# XB900.net
KiCad netlist of a schematic drawn in Altium Designer
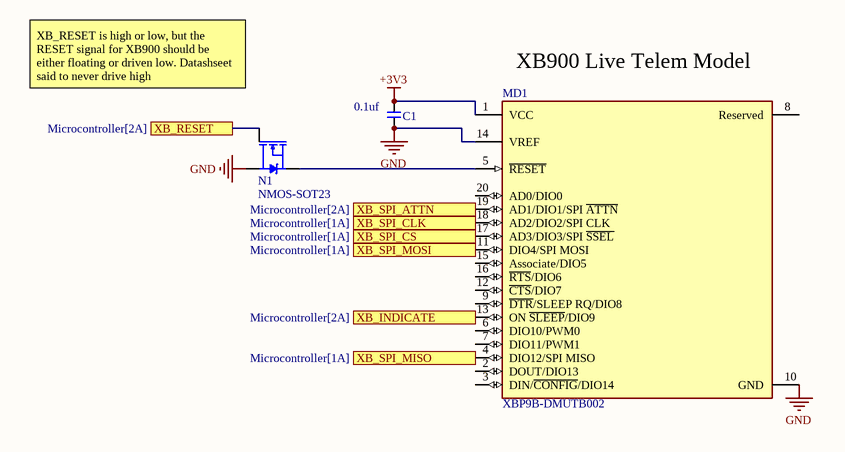
[diagram p0: XB900.SchDoc]

(export (version "E")
  (design (tool "Eeschema 10.0.6"))
  (components
    (comp (ref "C1")
      (value "0.1uf")
      (footprint "CAP-0603")
      (fields (field (name "SOURCE") "ife19_Elec_Library.SchLib"))
      (libsource (lib "Illini Formula Electric") (part "CAP-0603"))
    )
    (comp (ref "MD1")
      (value "XBP9B-DMUTB002")
      (footprint "FP-XBP9B-DMUTB002-MFG")
      (description "RX TXRX MOD ISM < 1GHZ U.FL TH")
      (libsource (lib "Altium Content Vault") (part "053d8e65a610ce00d52093c0e212ca3"))
    )
    (comp (ref "N1")
      (value "NMOS-SOT23")
      (footprint "SOT23")
      (fields (field (name "SOURCE") "ife19_Elec_Library.SchLib"))
      (libsource (lib "Illini Formula Electric") (part "NMOS-SOT23"))
    )
  )
  (nets
    (net (code "1") (name "+3V3") (class "Default")
      (node (ref "C1") (pin "2") (pinfunction "2_2") (pintype "passive"))
      (node (ref "MD1") (pin "1") (pinfunction "VCC_1") (pintype "power_in"))
    )
    (net (code "2") (name "/XB_INDICATE") (class "Default")
      (node (ref "MD1") (pin "13") (pinfunction "ON_~{SLEEP}/DIO9_13") (pintype "bidirectional"))
    )
    (net (code "3") (name "/XB_RESET") (class "Default")
      (node (ref "N1") (pin "1") (pinfunction "G_1") (pintype "passive"))
    )
    (net (code "4") (name "/XB_SPI_ATTN") (class "Default")
      (node (ref "MD1") (pin "19") (pinfunction "AD1/DIO1/SPI_~{ATTN}_19") (pintype "bidirectional"))
    )
    (net (code "5") (name "/XB_SPI_CLK") (class "Default")
      (node (ref "MD1") (pin "18") (pinfunction "AD2/DIO2/SPI_CLK_18") (pintype "bidirectional"))
    )
    (net (code "6") (name "/XB_SPI_CS") (class "Default")
      (node (ref "MD1") (pin "17") (pinfunction "AD3/DIO3/SPI_~{SSEL}_17") (pintype "bidirectional"))
    )
    (net (code "7") (name "/XB_SPI_MISO") (class "Default")
      (node (ref "MD1") (pin "4") (pinfunction "DIO12/SPI_MISO_4") (pintype "bidirectional"))
    )
    (net (code "8") (name "/XB_SPI_MOSI") (class "Default")
      (node (ref "MD1") (pin "11") (pinfunction "DIO4/SPI_MOSI_11") (pintype "bidirectional"))
    )
    (net (code "9") (name "GND") (class "Default")
      (node (ref "C1") (pin "1") (pinfunction "1_1") (pintype "passive"))
      (node (ref "MD1") (pin "10") (pinfunction "GND_10") (pintype "power_in"))
      (node (ref "MD1") (pin "14") (pinfunction "VREF_14") (pintype "passive"))
      (node (ref "N1") (pin "2") (pinfunction "S_2") (pintype "passive"))
    )
    (net (code "10") (name "Net-(MD1-~{RESET})") (class "Default")
      (node (ref "MD1") (pin "5") (pinfunction "~{RESET}_5") (pintype "input"))
      (node (ref "N1") (pin "3") (pinfunction "D_3") (pintype "passive"))
    )
    (net (code "11") (name "unconnected-(MD1-AD0{slash}DIO0-Pad20)") (class "Default")
      (node (ref "MD1") (pin "20") (pinfunction "AD0/DIO0_20") (pintype "bidirectional"))
    )
    (net (code "12") (name "unconnected-(MD1-Associate{slash}DIO5-Pad15)") (class "Default")
      (node (ref "MD1") (pin "15") (pinfunction "Associate/DIO5_15") (pintype "bidirectional"))
    )
    (net (code "13") (name "unconnected-(MD1-DIN{slash}~{CONFIG}{slash}DIO14-Pad3)") (class "Default")
      (node (ref "MD1") (pin "3") (pinfunction "DIN/~{CONFIG}/DIO14_3") (pintype "bidirectional"))
    )
    (net (code "14") (name "unconnected-(MD1-DIO10{slash}PWM0-Pad6)") (class "Default")
      (node (ref "MD1") (pin "6") (pinfunction "DIO10/PWM0_6") (pintype "bidirectional"))
    )
    (net (code "15") (name "unconnected-(MD1-DIO11{slash}PWM1-Pad7)") (class "Default")
      (node (ref "MD1") (pin "7") (pinfunction "DIO11/PWM1_7") (pintype "bidirectional"))
    )
    (net (code "16") (name "unconnected-(MD1-DOUT{slash}DIO13-Pad2)") (class "Default")
      (node (ref "MD1") (pin "2") (pinfunction "DOUT/DIO13_2") (pintype "bidirectional"))
    )
    (net (code "17") (name "unconnected-(MD1-Reserved-Pad8)") (class "Default")
      (node (ref "MD1") (pin "8") (pinfunction "Reserved_8") (pintype "passive"))
    )
    (net (code "18") (name "unconnected-(MD1-~{CTS}{slash}DIO7-Pad12)") (class "Default")
      (node (ref "MD1") (pin "12") (pinfunction "~{CTS}/DIO7_12") (pintype "bidirectional"))
    )
    (net (code "19") (name "unconnected-(MD1-~{DTR}{slash}SLEEP_RQ{slash}DIO8-Pad9)") (class "Default")
      (node (ref "MD1") (pin "9") (pinfunction "~{DTR}/SLEEP_RQ/DIO8_9") (pintype "bidirectional"))
    )
    (net (code "20") (name "unconnected-(MD1-~{RTS}{slash}DIO6-Pad16)") (class "Default")
      (node (ref "MD1") (pin "16") (pinfunction "~{RTS}/DIO6_16") (pintype "bidirectional"))
    )
  )
)
